# BusPirate-ng_v1_0.net
KiCad netlist of a schematic drawn in EAGLE
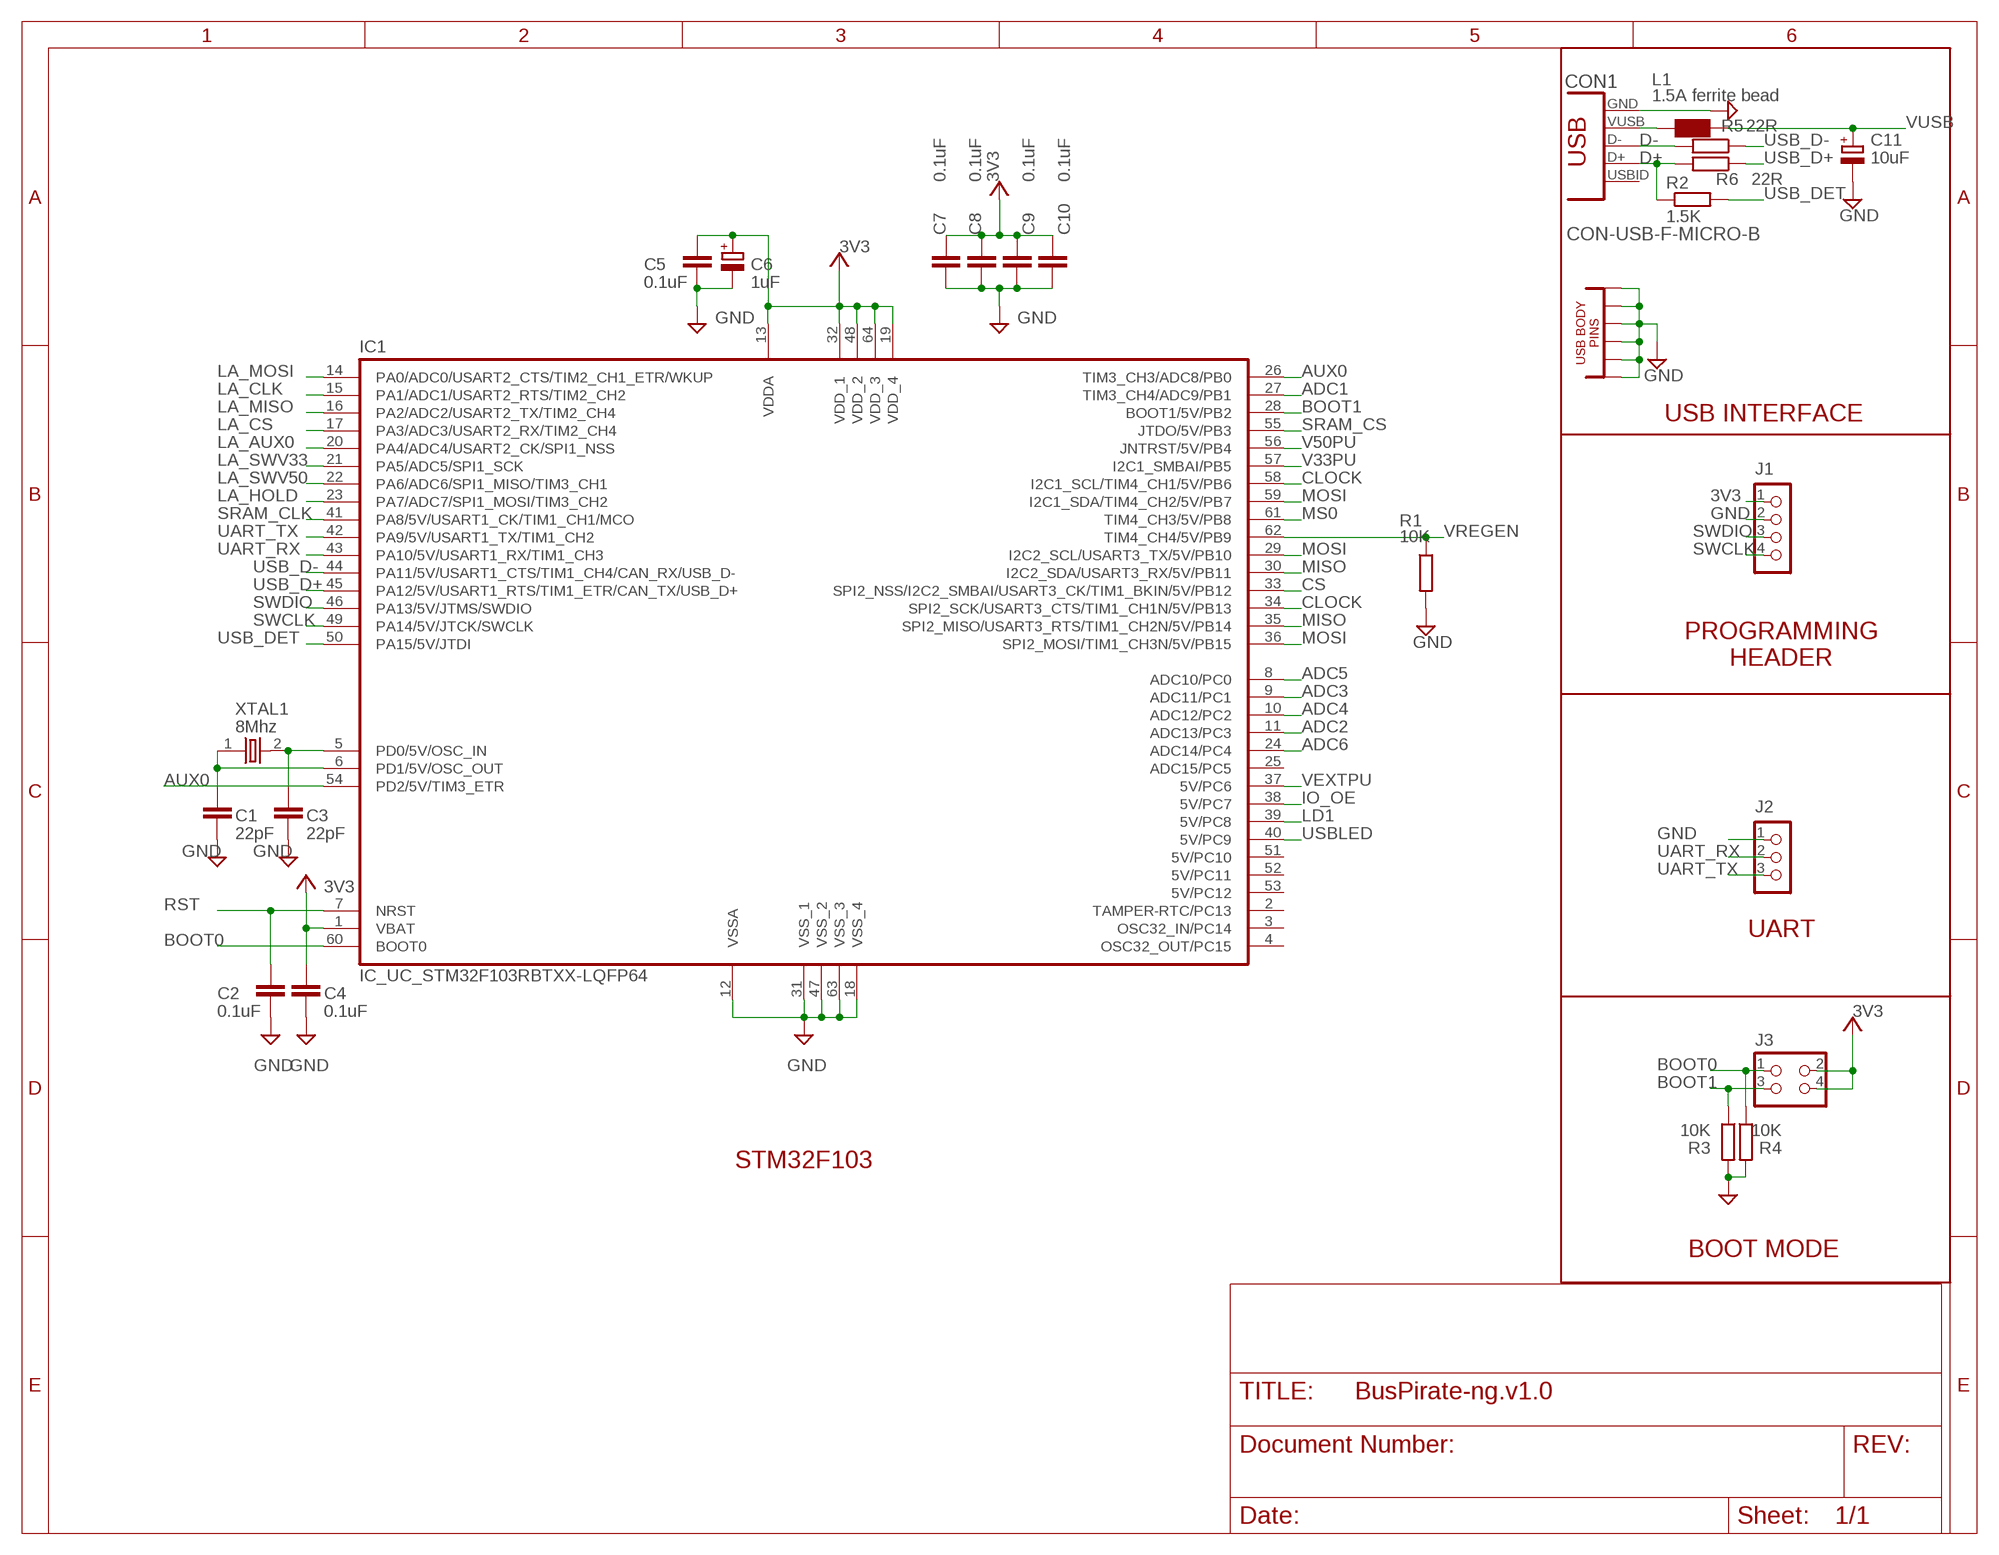
[diagram p0: schematic, sheet 1, part 1 of 2]
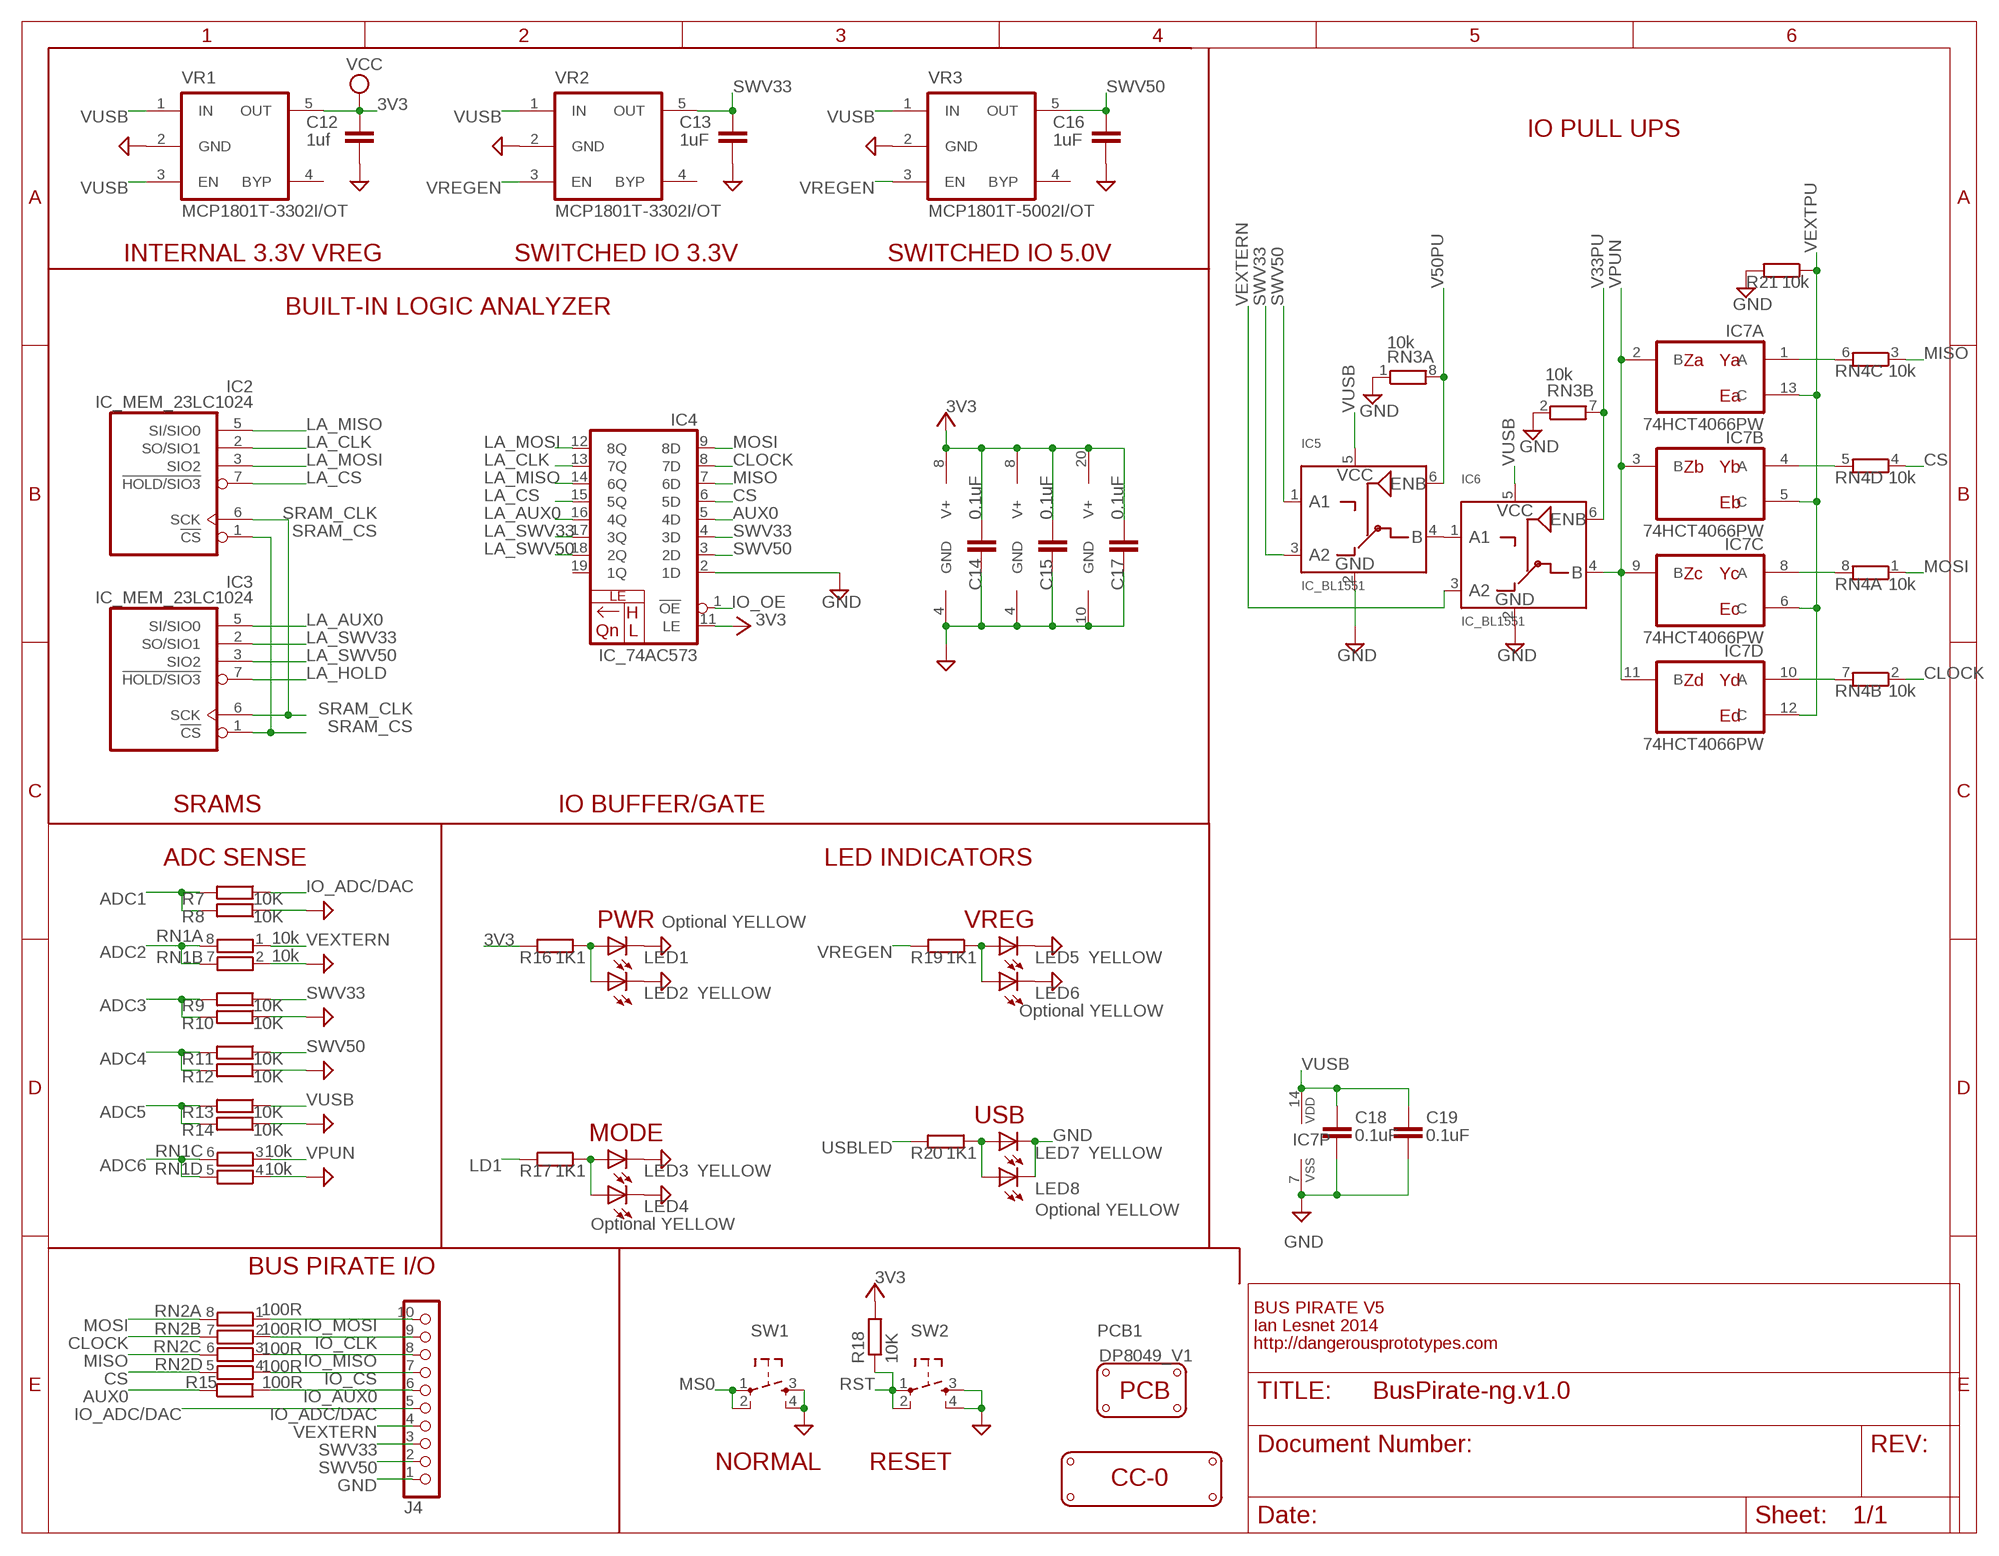
[diagram p1: schematic, sheet 1, part 2 of 2]

(export (version "E")
  (design (tool "Eeschema 10.0.6"))
  (components
    (comp (ref "C1")
      (value "22pF")
      (footprint "eagle-import:C0603")
      (libsource (lib "eagle-import") (part "C-EUC0603"))
    )
    (comp (ref "C2")
      (value "0.1uF")
      (footprint "eagle-import:C0603")
      (libsource (lib "eagle-import") (part "C-EUC0603"))
    )
    (comp (ref "C3")
      (value "22pF")
      (footprint "eagle-import:C0603")
      (libsource (lib "eagle-import") (part "C-EUC0603"))
    )
    (comp (ref "C4")
      (value "0.1uF")
      (footprint "eagle-import:C0603")
      (libsource (lib "eagle-import") (part "C-EUC0603"))
    )
    (comp (ref "C5")
      (value "0.1uF")
      (footprint "eagle-import:C0603")
      (libsource (lib "eagle-import") (part "C-EUC0603"))
    )
    (comp (ref "C6")
      (value "1uF")
      (footprint "eagle-import:SMC_A")
      (libsource (lib "eagle-import") (part "CPOL-EUSMCA"))
    )
    (comp (ref "C7")
      (value "0.1uF")
      (footprint "eagle-import:C0603")
      (libsource (lib "eagle-import") (part "C-EUC0603"))
    )
    (comp (ref "C8")
      (value "0.1uF")
      (footprint "eagle-import:C0603")
      (libsource (lib "eagle-import") (part "C-EUC0603"))
    )
    (comp (ref "C9")
      (value "0.1uF")
      (footprint "eagle-import:C0603")
      (libsource (lib "eagle-import") (part "C-EUC0603"))
    )
    (comp (ref "C10")
      (value "0.1uF")
      (footprint "eagle-import:C0603")
      (libsource (lib "eagle-import") (part "C-EUC0603"))
    )
    (comp (ref "C11")
      (value "10uF")
      (footprint "eagle-import:SMC_A")
      (libsource (lib "eagle-import") (part "CPOL-EUSMCA"))
    )
    (comp (ref "C12")
      (value "1uf")
      (footprint "eagle-import:C0603")
      (libsource (lib "eagle-import") (part "C-EUC0603"))
    )
    (comp (ref "C13")
      (value "1uF")
      (footprint "eagle-import:C0603")
      (libsource (lib "eagle-import") (part "C-EUC0603"))
    )
    (comp (ref "C14")
      (value "0.1uF")
      (footprint "eagle-import:C0603")
      (libsource (lib "eagle-import") (part "C-EUC0603"))
    )
    (comp (ref "C15")
      (value "0.1uF")
      (footprint "eagle-import:C0603")
      (libsource (lib "eagle-import") (part "C-EUC0603"))
    )
    (comp (ref "C16")
      (value "1uF")
      (footprint "eagle-import:C0603")
      (libsource (lib "eagle-import") (part "C-EUC0603"))
    )
    (comp (ref "C17")
      (value "0.1uF")
      (footprint "eagle-import:C0603")
      (libsource (lib "eagle-import") (part "C-EUC0603"))
    )
    (comp (ref "C18")
      (value "0.1uF")
      (footprint "eagle-import:C0603")
      (libsource (lib "eagle-import") (part "C-EUC0603"))
    )
    (comp (ref "C19")
      (value "0.1uF")
      (footprint "eagle-import:C0603")
      (libsource (lib "eagle-import") (part "C-EUC0603"))
    )
    (comp (ref "CON1")
      (value "CON-USB-F-MICRO-B")
      (footprint "eagle-import:CON_USB_MICRO-B-1-MD05SMXXX-01")
      (libsource (lib "eagle-import") (part "CON-USB-F-MICRO-B"))
    )
    (comp (ref "IC1")
      (value "IC_UC_STM32F103RBTXX-LQFP64")
      (footprint "eagle-import:LQFP64")
      (libsource (lib "eagle-import") (part "IC_UC_STM32F103RBTXX-LQFP64"))
    )
    (comp (ref "IC2")
      (value "IC_MEM_23LC1024")
      (footprint "eagle-import:SOIC-8")
      (libsource (lib "eagle-import") (part "IC_MEM_23LC1024"))
    )
    (comp (ref "IC3")
      (value "IC_MEM_23LC1024")
      (footprint "eagle-import:SOIC-8")
      (libsource (lib "eagle-import") (part "IC_MEM_23LC1024"))
    )
    (comp (ref "IC4")
      (value "IC_74AC573")
      (footprint "eagle-import:TSSOP-20")
      (libsource (lib "eagle-import") (part "IC_74AC573-TSSOP-20"))
    )
    (comp (ref "IC5")
      (value "IC_BL1551")
      (footprint "eagle-import:SOT-363")
      (libsource (lib "eagle-import") (part "IC_BL1551"))
    )
    (comp (ref "IC6")
      (value "IC_BL1551")
      (footprint "eagle-import:SOT-363")
      (libsource (lib "eagle-import") (part "IC_BL1551"))
    )
    (comp (ref "IC7")
      (value "74HCT4066PW")
      (footprint "eagle-import:40XX_TSSOP14")
      (libsource (lib "eagle-import") (part "4066TS"))
    )
    (comp (ref "J1")
      (value "CON_HEADER_1X04")
      (footprint "eagle-import:M1X4")
      (libsource (lib "eagle-import") (part "CON_HEADER_1X04"))
    )
    (comp (ref "J2")
      (value "CON_HEADER_1X03-PTH")
      (footprint "eagle-import:M1X3")
      (libsource (lib "eagle-import") (part "CON_HEADER_1X03-PTH"))
    )
    (comp (ref "J3")
      (value "CON_HEADER_2X02-PTH")
      (footprint "eagle-import:M2X2")
      (libsource (lib "eagle-import") (part "CON_HEADER_2X02-PTH"))
    )
    (comp (ref "J4")
      (value "CON_HEADER_1X10-RIGHT_ANGLED_PTH_SHROUDED")
      (footprint "eagle-import:M1X10_MALE_RIGHT_ANGLES_PTH_SHROUDED")
      (libsource (lib "eagle-import") (part "CON_HEADER_1X10-RIGHT_ANGLED_PTH_SHROUDED"))
    )
    (comp (ref "L1")
      (value "1.5A ferrite bead")
      (footprint "eagle-import:WE-KI_0805_B")
      (libsource (lib "eagle-import") (part "WE-KIL_0805"))
    )
    (comp (ref "LED1")
      (value "Optional YELLOW")
      (footprint "eagle-import:LED-805")
      (libsource (lib "eagle-import") (part "LED-0805"))
    )
    (comp (ref "LED2")
      (value "YELLOW")
      (footprint "eagle-import:LED-805")
      (libsource (lib "eagle-import") (part "LED-0805"))
    )
    (comp (ref "LED3")
      (value "YELLOW")
      (footprint "eagle-import:LED-805")
      (libsource (lib "eagle-import") (part "LED-0805"))
    )
    (comp (ref "LED4")
      (value "Optional YELLOW")
      (footprint "eagle-import:LED-805")
      (libsource (lib "eagle-import") (part "LED-0805"))
    )
    (comp (ref "LED5")
      (value "YELLOW")
      (footprint "eagle-import:LED-805")
      (libsource (lib "eagle-import") (part "LED-0805"))
    )
    (comp (ref "LED6")
      (value "Optional YELLOW")
      (footprint "eagle-import:LED-805")
      (libsource (lib "eagle-import") (part "LED-0805"))
    )
    (comp (ref "LED7")
      (value "YELLOW")
      (footprint "eagle-import:LED-805")
      (libsource (lib "eagle-import") (part "LED-0805"))
    )
    (comp (ref "LED8")
      (value "Optional YELLOW")
      (footprint "eagle-import:LED-805")
      (libsource (lib "eagle-import") (part "LED-0805"))
    )
    (comp (ref "LOGO1")
      (value "LOGO_CC-0")
      (footprint "eagle-import:LOGO_CC-0")
      (libsource (lib "eagle-import") (part "LOGO_CC-0"))
    )
    (comp (ref "PCB1")
      (value "PCB_DP_RECTANGLE-80X49")
      (footprint "eagle-import:DP8049_V1")
      (fields (field (name "PCB_SIZE") "DP8049_V1"))
      (libsource (lib "eagle-import") (part "PCB_DP_RECTANGLE-80X49"))
    )
    (comp (ref "R1")
      (value "10K")
      (footprint "eagle-import:R603")
      (libsource (lib "eagle-import") (part "RESISTOR-0603"))
    )
    (comp (ref "R2")
      (value "1.5K")
      (footprint "eagle-import:R603")
      (libsource (lib "eagle-import") (part "dp_devices.v6_RESISTOR-0603"))
    )
    (comp (ref "R3")
      (value "10K")
      (footprint "eagle-import:R0603")
      (libsource (lib "eagle-import") (part "R-EU_R0603"))
    )
    (comp (ref "R4")
      (value "10K")
      (footprint "eagle-import:R0603")
      (libsource (lib "eagle-import") (part "R-EU_R0603"))
    )
    (comp (ref "R5")
      (value "22R")
      (footprint "eagle-import:R603")
      (libsource (lib "eagle-import") (part "dp_devices.v6_RESISTOR-0603"))
    )
    (comp (ref "R6")
      (value "22R")
      (footprint "eagle-import:R603")
      (libsource (lib "eagle-import") (part "dp_devices.v6_RESISTOR-0603"))
    )
    (comp (ref "R7")
      (value "10K")
      (footprint "eagle-import:R0603")
      (libsource (lib "eagle-import") (part "resistor_R-EU_R0603"))
    )
    (comp (ref "R8")
      (value "10K")
      (footprint "eagle-import:R0603")
      (libsource (lib "eagle-import") (part "resistor_R-EU_R0603"))
    )
    (comp (ref "R9")
      (value "10K")
      (footprint "eagle-import:R0603")
      (libsource (lib "eagle-import") (part "resistor_R-EU_R0603"))
    )
    (comp (ref "R10")
      (value "10K")
      (footprint "eagle-import:R0603")
      (libsource (lib "eagle-import") (part "resistor_R-EU_R0603"))
    )
    (comp (ref "R11")
      (value "10K")
      (footprint "eagle-import:R0603")
      (libsource (lib "eagle-import") (part "resistor_R-EU_R0603"))
    )
    (comp (ref "R12")
      (value "10K")
      (footprint "eagle-import:R0603")
      (libsource (lib "eagle-import") (part "resistor_R-EU_R0603"))
    )
    (comp (ref "R13")
      (value "10K")
      (footprint "eagle-import:R0603")
      (libsource (lib "eagle-import") (part "resistor_R-EU_R0603"))
    )
    (comp (ref "R14")
      (value "10K")
      (footprint "eagle-import:R0603")
      (libsource (lib "eagle-import") (part "resistor_R-EU_R0603"))
    )
    (comp (ref "R15")
      (value "100R")
      (footprint "eagle-import:R603")
      (libsource (lib "eagle-import") (part "dp_devices.v6_RESISTOR-0603"))
    )
    (comp (ref "R16")
      (value "1K1")
      (footprint "eagle-import:R603")
      (libsource (lib "eagle-import") (part "RESISTOR-0603"))
    )
    (comp (ref "R17")
      (value "1K1")
      (footprint "eagle-import:R603")
      (libsource (lib "eagle-import") (part "RESISTOR-0603"))
    )
    (comp (ref "R18")
      (value "10K")
      (footprint "eagle-import:R603")
      (libsource (lib "eagle-import") (part "dp_devices.v6_RESISTOR-0603"))
    )
    (comp (ref "R19")
      (value "1K1")
      (footprint "eagle-import:R603")
      (libsource (lib "eagle-import") (part "RESISTOR-0603"))
    )
    (comp (ref "R20")
      (value "1K1")
      (footprint "eagle-import:R603")
      (libsource (lib "eagle-import") (part "RESISTOR-0603"))
    )
    (comp (ref "R21")
      (value "10k")
      (footprint "eagle-import:R603")
      (libsource (lib "eagle-import") (part "RESISTOR-0603"))
    )
    (comp (ref "RN1")
      (value "10k")
      (footprint "eagle-import:RN8P-4R-CRA06S")
      (libsource (lib "eagle-import") (part "RNETWORK"))
    )
    (comp (ref "RN2")
      (value "100R")
      (footprint "eagle-import:RN8P-4R-CRA06S")
      (libsource (lib "eagle-import") (part "RNETWORK"))
    )
    (comp (ref "RN3")
      (value "10k")
      (footprint "eagle-import:RN8P-4R-CRA06S")
      (libsource (lib "eagle-import") (part "RNETWORK"))
    )
    (comp (ref "RN4")
      (value "10k")
      (footprint "eagle-import:RN8P-4R-CRA06S")
      (libsource (lib "eagle-import") (part "RNETWORK"))
    )
    (comp (ref "SW1")
      (value "SW_TACT_4P")
      (footprint "eagle-import:SW_TACT_SMALL")
      (libsource (lib "eagle-import") (part "SW_TACT_4P"))
    )
    (comp (ref "SW2")
      (value "SW_TACT_4P")
      (footprint "eagle-import:SW_TACT_SMALL")
      (libsource (lib "eagle-import") (part "SW_TACT_4P"))
    )
    (comp (ref "VR1")
      (value "MCP1801T-3302I/OT")
      (footprint "eagle-import:SOT-23-5@1")
      (libsource (lib "eagle-import") (part "MIC5205"))
    )
    (comp (ref "VR2")
      (value "MCP1801T-3302I/OT")
      (footprint "eagle-import:SOT-23-5@1")
      (libsource (lib "eagle-import") (part "MIC5205"))
    )
    (comp (ref "VR3")
      (value "MCP1801T-5002I/OT")
      (footprint "eagle-import:SOT-23-5@1")
      (libsource (lib "eagle-import") (part "MIC5205"))
    )
    (comp (ref "XTAL1")
      (value "8Mhz")
      (footprint "eagle-import:XTAL_4X6")
      (libsource (lib "eagle-import") (part "OSC-XTAL-12M"))
    )
  )
  (nets
    (net (code "1") (name "/ADC1") (class "Default")
      (node (ref "IC1") (pin "27") (pinfunction "TIM3_CH4/ADC9/PB1_27") (pintype "bidirectional"))
      (node (ref "R7") (pin "2") (pinfunction "2_2") (pintype "passive"))
      (node (ref "R8") (pin "2") (pinfunction "2_2") (pintype "passive"))
    )
    (net (code "2") (name "/ADC2") (class "Default")
      (node (ref "IC1") (pin "11") (pinfunction "ADC13/PC3_11") (pintype "bidirectional"))
      (node (ref "RN1") (pin "7") (pinfunction "2_7") (pintype "passive"))
      (node (ref "RN1") (pin "8") (pinfunction "2_8") (pintype "passive"))
    )
    (net (code "3") (name "/ADC3") (class "Default")
      (node (ref "IC1") (pin "9") (pinfunction "ADC11/PC1_9") (pintype "bidirectional"))
      (node (ref "R10") (pin "2") (pinfunction "2_2") (pintype "passive"))
      (node (ref "R9") (pin "2") (pinfunction "2_2") (pintype "passive"))
    )
    (net (code "4") (name "/ADC4") (class "Default")
      (node (ref "IC1") (pin "10") (pinfunction "ADC12/PC2_10") (pintype "bidirectional"))
      (node (ref "R11") (pin "2") (pinfunction "2_2") (pintype "passive"))
      (node (ref "R12") (pin "2") (pinfunction "2_2") (pintype "passive"))
    )
    (net (code "5") (name "/ADC5") (class "Default")
      (node (ref "IC1") (pin "8") (pinfunction "ADC10/PC0_8") (pintype "bidirectional"))
      (node (ref "R13") (pin "2") (pinfunction "2_2") (pintype "passive"))
      (node (ref "R14") (pin "2") (pinfunction "2_2") (pintype "passive"))
    )
    (net (code "6") (name "/ADC6") (class "Default")
      (node (ref "IC1") (pin "24") (pinfunction "ADC14/PC4_24") (pintype "bidirectional"))
      (node (ref "RN1") (pin "5") (pinfunction "2_5") (pintype "passive"))
      (node (ref "RN1") (pin "6") (pinfunction "2_6") (pintype "passive"))
    )
    (net (code "7") (name "/AUX0") (class "Default")
      (node (ref "IC1") (pin "26") (pinfunction "TIM3_CH3/ADC8/PB0_26") (pintype "bidirectional"))
      (node (ref "IC1") (pin "54") (pinfunction "PD2/5V/TIM3_ETR_54") (pintype "bidirectional"))
      (node (ref "IC4") (pin "5") (pinfunction "4D_5") (pintype "bidirectional"))
      (node (ref "R15") (pin "1") (pinfunction "1_1") (pintype "passive"))
    )
    (net (code "8") (name "/BOOT0") (class "Default")
      (node (ref "IC1") (pin "60") (pinfunction "BOOT0_60") (pintype "input"))
      (node (ref "J3") (pin "1") (pinfunction "1_1") (pintype "passive"))
      (node (ref "R4") (pin "1") (pinfunction "1_1") (pintype "passive"))
    )
    (net (code "9") (name "/BOOT1") (class "Default")
      (node (ref "IC1") (pin "28") (pinfunction "BOOT1/5V/PB2_28") (pintype "bidirectional"))
      (node (ref "J3") (pin "3") (pinfunction "3_3") (pintype "passive"))
      (node (ref "R3") (pin "1") (pinfunction "1_1") (pintype "passive"))
    )
    (net (code "10") (name "/CLOCK") (class "Default")
      (node (ref "IC1") (pin "34") (pinfunction "SPI2_SCK/USART3_CTS/TIM1_CH1N/5V/PB13_34") (pintype "bidirectional"))
      (node (ref "IC1") (pin "58") (pinfunction "I2C1_SCL/TIM4_CH1/5V/PB6_58") (pintype "bidirectional"))
      (node (ref "IC4") (pin "8") (pinfunction "7D_8") (pintype "bidirectional"))
      (node (ref "RN2") (pin "7") (pinfunction "2_7") (pintype "passive"))
      (node (ref "RN4") (pin "2") (pinfunction "1_2") (pintype "passive"))
    )
    (net (code "11") (name "/CS") (class "Default")
      (node (ref "IC1") (pin "33") (pinfunction "SPI2_NSS/I2C2_SMBAI/USART3_CK/TIM1_BKIN/5V/PB12_33") (pintype "bidirectional"))
      (node (ref "IC4") (pin "6") (pinfunction "5D_6") (pintype "bidirectional"))
      (node (ref "RN2") (pin "5") (pinfunction "2_5") (pintype "passive"))
      (node (ref "RN4") (pin "4") (pinfunction "1_4") (pintype "passive"))
    )
    (net (code "12") (name "/D+") (class "Default")
      (node (ref "CON1") (pin "P3") (pinfunction "D+_P3") (pintype "bidirectional"))
      (node (ref "R2") (pin "1") (pinfunction "1_1") (pintype "passive"))
      (node (ref "R6") (pin "2") (pinfunction "2_2") (pintype "passive"))
    )
    (net (code "13") (name "/D-") (class "Default")
      (node (ref "CON1") (pin "P2") (pinfunction "D-_P2") (pintype "bidirectional"))
      (node (ref "R5") (pin "2") (pinfunction "2_2") (pintype "passive"))
    )
    (net (code "14") (name "/IO_ADC{slash}DAC") (class "Default")
      (node (ref "J4") (pin "5") (pinfunction "5_5") (pintype "passive"))
      (node (ref "R7") (pin "1") (pinfunction "1_1") (pintype "passive"))
    )
    (net (code "15") (name "/IO_AUX0") (class "Default")
      (node (ref "J4") (pin "6") (pinfunction "6_6") (pintype "passive"))
      (node (ref "R15") (pin "2") (pinfunction "2_2") (pintype "passive"))
    )
    (net (code "16") (name "/IO_CLK") (class "Default")
      (node (ref "J4") (pin "9") (pinfunction "9_9") (pintype "passive"))
      (node (ref "RN2") (pin "2") (pinfunction "1_2") (pintype "passive"))
    )
    (net (code "17") (name "/IO_CS") (class "Default")
      (node (ref "J4") (pin "7") (pinfunction "7_7") (pintype "passive"))
      (node (ref "RN2") (pin "4") (pinfunction "1_4") (pintype "passive"))
    )
    (net (code "18") (name "/IO_MISO") (class "Default")
      (node (ref "J4") (pin "8") (pinfunction "8_8") (pintype "passive"))
      (node (ref "RN2") (pin "3") (pinfunction "1_3") (pintype "passive"))
    )
    (net (code "19") (name "/IO_MOSI") (class "Default")
      (node (ref "J4") (pin "10") (pinfunction "10_10") (pintype "passive"))
      (node (ref "RN2") (pin "1") (pinfunction "1_1") (pintype "passive"))
    )
    (net (code "20") (name "/IO_OE") (class "Default")
      (node (ref "IC1") (pin "38") (pinfunction "5V/PC7_38") (pintype "bidirectional"))
      (node (ref "IC4") (pin "1") (pinfunction "~{OE}_1") (pintype "input"))
    )
    (net (code "21") (name "/LA_AUX0") (class "Default")
      (node (ref "IC1") (pin "20") (pinfunction "PA4/ADC4/USART2_CK/SPI1_NSS_20") (pintype "bidirectional"))
      (node (ref "IC3") (pin "5") (pinfunction "SI/SIO0_5") (pintype "bidirectional"))
      (node (ref "IC4") (pin "16") (pinfunction "4Q_16") (pintype "bidirectional"))
    )
    (net (code "22") (name "/LA_CLK") (class "Default")
      (node (ref "IC1") (pin "15") (pinfunction "PA1/ADC1/USART2_RTS/TIM2_CH2_15") (pintype "bidirectional"))
      (node (ref "IC2") (pin "2") (pinfunction "SO/SIO1_2") (pintype "bidirectional"))
      (node (ref "IC4") (pin "13") (pinfunction "7Q_13") (pintype "bidirectional"))
    )
    (net (code "23") (name "/LA_CS") (class "Default")
      (node (ref "IC1") (pin "17") (pinfunction "PA3/ADC3/USART2_RX/TIM2_CH4_17") (pintype "bidirectional"))
      (node (ref "IC2") (pin "7") (pinfunction "~{HOLD/SIO3}_7") (pintype "input"))
      (node (ref "IC4") (pin "15") (pinfunction "5Q_15") (pintype "bidirectional"))
    )
    (net (code "24") (name "/LA_HOLD") (class "Default")
      (node (ref "IC1") (pin "23") (pinfunction "PA7/ADC7/SPI1_MOSI/TIM3_CH2_23") (pintype "bidirectional"))
      (node (ref "IC3") (pin "7") (pinfunction "~{HOLD/SIO3}_7") (pintype "input"))
    )
    (net (code "25") (name "/LA_MISO") (class "Default")
      (node (ref "IC1") (pin "16") (pinfunction "PA2/ADC2/USART2_TX/TIM2_CH4_16") (pintype "bidirectional"))
      (node (ref "IC2") (pin "5") (pinfunction "SI/SIO0_5") (pintype "bidirectional"))
      (node (ref "IC4") (pin "14") (pinfunction "6Q_14") (pintype "bidirectional"))
    )
    (net (code "26") (name "/LA_MOSI") (class "Default")
      (node (ref "IC1") (pin "14") (pinfunction "PA0/ADC0/USART2_CTS/TIM2_CH1_ETR/WKUP_14") (pintype "bidirectional"))
      (node (ref "IC2") (pin "3") (pinfunction "SIO2_3") (pintype "bidirectional"))
      (node (ref "IC4") (pin "12") (pinfunction "8Q_12") (pintype "bidirectional"))
    )
    (net (code "27") (name "/LA_SWV33") (class "Default")
      (node (ref "IC1") (pin "21") (pinfunction "PA5/ADC5/SPI1_SCK_21") (pintype "bidirectional"))
      (node (ref "IC3") (pin "2") (pinfunction "SO/SIO1_2") (pintype "bidirectional"))
      (node (ref "IC4") (pin "17") (pinfunction "3Q_17") (pintype "bidirectional"))
    )
    (net (code "28") (name "/LA_SWV50") (class "Default")
      (node (ref "IC1") (pin "22") (pinfunction "PA6/ADC6/SPI1_MISO/TIM3_CH1_22") (pintype "bidirectional"))
      (node (ref "IC3") (pin "3") (pinfunction "SIO2_3") (pintype "bidirectional"))
      (node (ref "IC4") (pin "18") (pinfunction "2Q_18") (pintype "bidirectional"))
    )
    (net (code "29") (name "/LD1") (class "Default")
      (node (ref "IC1") (pin "39") (pinfunction "5V/PC8_39") (pintype "bidirectional"))
      (node (ref "R17") (pin "2") (pinfunction "2_2") (pintype "passive"))
    )
    (net (code "30") (name "/MISO") (class "Default")
      (node (ref "IC1") (pin "30") (pinfunction "I2C2_SDA/USART3_RX/5V/PB11_30") (pintype "bidirectional"))
      (node (ref "IC1") (pin "35") (pinfunction "SPI2_MISO/USART3_RTS/TIM1_CH2N/5V/PB14_35") (pintype "bidirectional"))
      (node (ref "IC4") (pin "7") (pinfunction "6D_7") (pintype "bidirectional"))
      (node (ref "RN2") (pin "6") (pinfunction "2_6") (pintype "passive"))
      (node (ref "RN4") (pin "3") (pinfunction "1_3") (pintype "passive"))
    )
    (net (code "31") (name "/MOSI") (class "Default")
      (node (ref "IC1") (pin "29") (pinfunction "I2C2_SCL/USART3_TX/5V/PB10_29") (pintype "bidirectional"))
      (node (ref "IC1") (pin "36") (pinfunction "SPI2_MOSI/TIM1_CH3N/5V/PB15_36") (pintype "bidirectional"))
      (node (ref "IC1") (pin "59") (pinfunction "I2C1_SDA/TIM4_CH2/5V/PB7_59") (pintype "bidirectional"))
      (node (ref "IC4") (pin "9") (pinfunction "8D_9") (pintype "bidirectional"))
      (node (ref "RN2") (pin "8") (pinfunction "2_8") (pintype "passive"))
      (node (ref "RN4") (pin "1") (pinfunction "1_1") (pintype "passive"))
    )
    (net (code "32") (name "/MS0") (class "Default")
      (node (ref "IC1") (pin "61") (pinfunction "TIM4_CH3/5V/PB8_61") (pintype "bidirectional"))
      (node (ref "SW1") (pin "1") (pinfunction "1_1") (pintype "passive"))
      (node (ref "SW1") (pin "2") (pinfunction "2_2") (pintype "passive"))
    )
    (net (code "33") (name "/RST") (class "Default")
      (node (ref "C2") (pin "2") (pinfunction "2_2") (pintype "passive"))
      (node (ref "IC1") (pin "7") (pinfunction "NRST_7") (pintype "bidirectional"))
      (node (ref "R18") (pin "1") (pinfunction "1_1") (pintype "passive"))
      (node (ref "SW2") (pin "1") (pinfunction "1_1") (pintype "passive"))
      (node (ref "SW2") (pin "2") (pinfunction "2_2") (pintype "passive"))
    )
    (net (code "34") (name "/SRAM_CLK") (class "Default")
      (node (ref "IC1") (pin "41") (pinfunction "PA8/5V/USART1_CK/TIM1_CH1/MCO_41") (pintype "bidirectional"))
      (node (ref "IC2") (pin "6") (pinfunction "SCK_6") (pintype "input"))
      (node (ref "IC3") (pin "6") (pinfunction "SCK_6") (pintype "input"))
    )
    (net (code "35") (name "/SRAM_CS") (class "Default")
      (node (ref "IC1") (pin "55") (pinfunction "JTDO/5V/PB3_55") (pintype "bidirectional"))
      (node (ref "IC2") (pin "1") (pinfunction "~{CS}_1") (pintype "input"))
      (node (ref "IC3") (pin "1") (pinfunction "~{CS}_1") (pintype "input"))
    )
    (net (code "36") (name "/SWCLK") (class "Default")
      (node (ref "IC1") (pin "49") (pinfunction "PA14/5V/JTCK/SWCLK_49") (pintype "bidirectional"))
      (node (ref "J1") (pin "4") (pinfunction "4_4") (pintype "bidirectional"))
    )
    (net (code "37") (name "/SWDIO") (class "Default")
      (node (ref "IC1") (pin "46") (pinfunction "PA13/5V/JTMS/SWDIO_46") (pintype "bidirectional"))
      (node (ref "J1") (pin "3") (pinfunction "3_3") (pintype "bidirectional"))
    )
    (net (code "38") (name "/SWV33") (class "Default")
      (node (ref "C13") (pin "1") (pinfunction "1_1") (pintype "passive"))
      (node (ref "IC4") (pin "4") (pinfunction "3D_4") (pintype "bidirectional"))
      (node (ref "IC5") (pin "3") (pinfunction "A2_3") (pintype "input"))
      (node (ref "J4") (pin "3") (pinfunction "3_3") (pintype "passive"))
      (node (ref "R9") (pin "1") (pinfunction "1_1") (pintype "passive"))
      (node (ref "VR2") (pin "5") (pinfunction "OUT_5") (pintype "bidirectional"))
    )
    (net (code "39") (name "/SWV50") (class "Default")
      (node (ref "C16") (pin "1") (pinfunction "1_1") (pintype "passive"))
      (node (ref "IC4") (pin "3") (pinfunction "2D_3") (pintype "bidirectional"))
      (node (ref "IC5") (pin "1") (pinfunction "A1_1") (pintype "input"))
      (node (ref "J4") (pin "2") (pinfunction "2_2") (pintype "passive"))
      (node (ref "R11") (pin "1") (pinfunction "1_1") (pintype "passive"))
      (node (ref "VR3") (pin "5") (pinfunction "OUT_5") (pintype "bidirectional"))
    )
    (net (code "40") (name "/UART_RX") (class "Default")
      (node (ref "IC1") (pin "43") (pinfunction "PA10/5V/USART1_RX/TIM1_CH3_43") (pintype "bidirectional"))
      (node (ref "J2") (pin "2") (pinfunction "2_2") (pintype "bidirectional"))
    )
    (net (code "41") (name "/UART_TX") (class "Default")
      (node (ref "IC1") (pin "42") (pinfunction "PA9/5V/USART1_TX/TIM1_CH2_42") (pintype "bidirectional"))
      (node (ref "J2") (pin "3") (pinfunction "3_3") (pintype "bidirectional"))
    )
    (net (code "42") (name "/USBLED") (class "Default")
      (node (ref "IC1") (pin "40") (pinfunction "5V/PC9_40") (pintype "bidirectional"))
      (node (ref "R20") (pin "2") (pinfunction "2_2") (pintype "passive"))
    )
    (net (code "43") (name "/USB_D+") (class "Default")
      (node (ref "IC1") (pin "45") (pinfunction "PA12/5V/USART1_RTS/TIM1_ETR/CAN_TX/USB_D+_45") (pintype "bidirectional"))
      (node (ref "R6") (pin "1") (pinfunction "1_1") (pintype "passive"))
    )
    (net (code "44") (name "/USB_D-") (class "Default")
      (node (ref "IC1") (pin "44") (pinfunction "PA11/5V/USART1_CTS/TIM1_CH4/CAN_RX/USB_D-_44") (pintype "bidirectional"))
      (node (ref "R5") (pin "1") (pinfunction "1_1") (pintype "passive"))
    )
    (net (code "45") (name "/USB_DET") (class "Default")
      (node (ref "IC1") (pin "50") (pinfunction "PA15/5V/JTDI_50") (pintype "bidirectional"))
      (node (ref "R2") (pin "2") (pinfunction "2_2") (pintype "passive"))
    )
    (net (code "46") (name "/V33PU") (class "Default")
      (node (ref "IC1") (pin "57") (pinfunction "I2C1_SMBAI/PB5_57") (pintype "bidirectional"))
      (node (ref "IC6") (pin "6") (pinfunction "ENB_6") (pintype "input"))
      (node (ref "RN3") (pin "7") (pinfunction "2_7") (pintype "passive"))
    )
    (net (code "47") (name "/V50PU") (class "Default")
      (node (ref "IC1") (pin "56") (pinfunction "JNTRST/5V/PB4_56") (pintype "bidirectional"))
      (node (ref "IC5") (pin "6") (pinfunction "ENB_6") (pintype "input"))
      (node (ref "RN3") (pin "8") (pinfunction "2_8") (pintype "passive"))
    )
    (net (code "48") (name "/VEXTERN") (class "Default")
      (node (ref "IC6") (pin "3") (pinfunction "A2_3") (pintype "input"))
      (node (ref "J4") (pin "4") (pinfunction "4_4") (pintype "passive"))
      (node (ref "RN1") (pin "1") (pinfunction "1_1") (pintype "passive"))
    )
    (net (code "49") (name "/VEXTPU") (class "Default")
      (node (ref "IC1") (pin "37") (pinfunction "5V/PC6_37") (pintype "bidirectional"))
      (node (ref "IC7") (pin "12") (pinfunction "C_12") (pintype "input"))
      (node (ref "IC7") (pin "13") (pinfunction "C_13") (pintype "input"))
      (node (ref "IC7") (pin "5") (pinfunction "C_5") (pintype "input"))
      (node (ref "IC7") (pin "6") (pinfunction "C_6") (pintype "input"))
      (node (ref "R21") (pin "1") (pinfunction "1_1") (pintype "passive"))
    )
    (net (code "50") (name "/VPUN") (class "Default")
      (node (ref "IC6") (pin "4") (pinfunction "B_4") (pintype "output"))
      (node (ref "IC7") (pin "11") (pinfunction "B_11") (pintype "tri_state"))
      (node (ref "IC7") (pin "2") (pinfunction "B_2") (pintype "tri_state"))
      (node (ref "IC7") (pin "3") (pinfunction "B_3") (pintype "tri_state"))
      (node (ref "IC7") (pin "9") (pinfunction "B_9") (pintype "tri_state"))
      (node (ref "RN1") (pin "3") (pinfunction "1_3") (pintype "passive"))
    )
    (net (code "51") (name "/VREGEN") (class "Default")
      (node (ref "IC1") (pin "62") (pinfunction "TIM4_CH4/5V/PB9_62") (pintype "bidirectional"))
      (node (ref "R1") (pin "1") (pinfunction "1_1") (pintype "passive"))
      (node (ref "R19") (pin "2") (pinfunction "2_2") (pintype "passive"))
      (node (ref "VR2") (pin "3") (pinfunction "EN_3") (pintype "bidirectional"))
      (node (ref "VR3") (pin "3") (pinfunction "EN_3") (pintype "bidirectional"))
    )
    (net (code "52") (name "/VUSB") (class "Default")
      (node (ref "C11") (pin "+") (pinfunction "+_+") (pintype "passive"))
      (node (ref "C18") (pin "1") (pinfunction "1_1") (pintype "passive"))
      (node (ref "C19") (pin "1") (pinfunction "1_1") (pintype "passive"))
      (node (ref "IC5") (pin "5") (pinfunction "VCC_5") (pintype "power_in"))
      (node (ref "IC6") (pin "5") (pinfunction "VCC_5") (pintype "power_in"))
      (node (ref "IC7") (pin "14") (pinfunction "VDD_14") (pintype "power_in"))
      (node (ref "L1") (pin "1") (pinfunction "2_1") (pintype "passive"))
      (node (ref "R13") (pin "1") (pinfunction "1_1") (pintype "passive"))
      (node (ref "VR1") (pin "1") (pinfunction "IN_1") (pintype "bidirectional"))
      (node (ref "VR1") (pin "3") (pinfunction "EN_3") (pintype "bidirectional"))
      (node (ref "VR2") (pin "1") (pinfunction "IN_1") (pintype "bidirectional"))
      (node (ref "VR3") (pin "1") (pinfunction "IN_1") (pintype "bidirectional"))
    )
    (net (code "53") (name "GND") (class "Default")
      (node (ref "C1") (pin "1") (pinfunction "1_1") (pintype "passive"))
      (node (ref "C10") (pin "1") (pinfunction "1_1") (pintype "passive"))
      (node (ref "C11") (pin "-") (pinfunction "-_-") (pintype "passive"))
      (node (ref "C12") (pin "2") (pinfunction "2_2") (pintype "passive"))
      (node (ref "C13") (pin "2") (pinfunction "2_2") (pintype "passive"))
      (node (ref "C14") (pin "2") (pinfunction "2_2") (pintype "passive"))
      (node (ref "C15") (pin "2") (pinfunction "2_2") (pintype "passive"))
      (node (ref "C16") (pin "2") (pinfunction "2_2") (pintype "passive"))
      (node (ref "C17") (pin "2") (pinfunction "2_2") (pintype "passive"))
      (node (ref "C18") (pin "2") (pinfunction "2_2") (pintype "passive"))
      (node (ref "C19") (pin "2") (pinfunction "2_2") (pintype "passive"))
      (node (ref "C2") (pin "1") (pinfunction "1_1") (pintype "passive"))
      (node (ref "C3") (pin "1") (pinfunction "1_1") (pintype "passive"))
      (node (ref "C4") (pin "1") (pinfunction "1_1") (pintype "passive"))
      (node (ref "C5") (pin "1") (pinfunction "1_1") (pintype "passive"))
      (node (ref "C6") (pin "-") (pinfunction "-_-") (pintype "passive"))
      (node (ref "C7") (pin "1") (pinfunction "1_1") (pintype "passive"))
      (node (ref "C8") (pin "1") (pinfunction "1_1") (pintype "passive"))
      (node (ref "C9") (pin "1") (pinfunction "1_1") (pintype "passive"))
      (node (ref "CON1") (pin "GND1") (pinfunction "P$1_GND1") (pintype "passive"))
      (node (ref "CON1") (pin "GND2") (pinfunction "P$2_GND2") (pintype "passive"))
      (node (ref "CON1") (pin "GND3") (pinfunction "P$3_GND3") (pintype "passive"))
      (node (ref "CON1") (pin "GND4") (pinfunction "P$4_GND4") (pintype "passive"))
      (node (ref "CON1") (pin "GND5") (pinfunction "P$5_GND5") (pintype "passive"))
      (node (ref "CON1") (pin "GND6") (pinfunction "P$6_GND6") (pintype "passive"))
      (node (ref "CON1") (pin "P5") (pinfunction "GND_P5") (pintype "bidirectional"))
      (node (ref "IC1") (pin "12") (pinfunction "VSSA_12") (pintype "power_in"))
      (node (ref "IC1") (pin "18") (pinfunction "VSS_4_18") (pintype "power_in"))
      (node (ref "IC1") (pin "31") (pinfunction "VSS_1_31") (pintype "power_in"))
      (node (ref "IC1") (pin "47") (pinfunction "VSS_2_47") (pintype "power_in"))
      (node (ref "IC1") (pin "63") (pinfunction "VSS_3_63") (pintype "power_in"))
      (node (ref "IC2") (pin "4") (pinfunction "GND_4") (pintype "power_in"))
      (node (ref "IC3") (pin "4") (pinfunction "GND_4") (pintype "power_in"))
      (node (ref "IC4") (pin "10") (pinfunction "GND_10") (pintype "power_in"))
      (node (ref "IC4") (pin "2") (pinfunction "1D_2") (pintype "bidirectional"))
      (node (ref "IC5") (pin "2") (pinfunction "GND_2") (pintype "power_in"))
      (node (ref "IC6") (pin "2") (pinfunction "GND_2") (pintype "power_in"))
      (node (ref "IC7") (pin "7") (pinfunction "VSS_7") (pintype "power_in"))
      (node (ref "J1") (pin "2") (pinfunction "2_2") (pintype "bidirectional"))
      (node (ref "J2") (pin "1") (pinfunction "1_1") (pintype "bidirectional"))
      (node (ref "J4") (pin "1") (pinfunction "1_1") (pintype "passive"))
      (node (ref "LED1") (pin "C") (pinfunction "C_C") (pintype "passive"))
      (node (ref "LED2") (pin "C") (pinfunction "C_C") (pintype "passive"))
      (node (ref "LED3") (pin "C") (pinfunction "C_C") (pintype "passive"))
      (node (ref "LED4") (pin "C") (pinfunction "C_C") (pintype "passive"))
      (node (ref "LED5") (pin "C") (pinfunction "C_C") (pintype "passive"))
      (node (ref "LED6") (pin "C") (pinfunction "C_C") (pintype "passive"))
      (node (ref "LED7") (pin "C") (pinfunction "C_C") (pintype "passive"))
      (node (ref "LED8") (pin "C") (pinfunction "C_C") (pintype "passive"))
      (node (ref "R1") (pin "2") (pinfunction "2_2") (pintype "passive"))
      (node (ref "R10") (pin "1") (pinfunction "1_1") (pintype "passive"))
      (node (ref "R12") (pin "1") (pinfunction "1_1") (pintype "passive"))
      (node (ref "R14") (pin "1") (pinfunction "1_1") (pintype "passive"))
      (node (ref "R21") (pin "2") (pinfunction "2_2") (pintype "passive"))
      (node (ref "R3") (pin "2") (pinfunction "2_2") (pintype "passive"))
      (node (ref "R4") (pin "2") (pinfunction "2_2") (pintype "passive"))
      (node (ref "R8") (pin "1") (pinfunction "1_1") (pintype "passive"))
      (node (ref "RN1") (pin "2") (pinfunction "1_2") (pintype "passive"))
      (node (ref "RN1") (pin "4") (pinfunction "1_4") (pintype "passive"))
      (node (ref "RN3") (pin "1") (pinfunction "1_1") (pintype "passive"))
      (node (ref "RN3") (pin "2") (pinfunction "1_2") (pintype "passive"))
      (node (ref "SW1") (pin "3") (pinfunction "3_3") (pintype "passive"))
      (node (ref "SW1") (pin "4") (pinfunction "4_4") (pintype "passive"))
      (node (ref "SW2") (pin "3") (pinfunction "3_3") (pintype "passive"))
      (node (ref "SW2") (pin "4") (pinfunction "4_4") (pintype "passive"))
      (node (ref "VR1") (pin "2") (pinfunction "GND_2") (pintype "bidirectional"))
      (node (ref "VR2") (pin "2") (pinfunction "GND_2") (pintype "bidirectional"))
      (node (ref "VR3") (pin "2") (pinfunction "GND_2") (pintype "bidirectional"))
    )
    (net (code "54") (name "Net-(CON1A-VUSB)") (class "Default")
      (node (ref "CON1") (pin "P1") (pinfunction "VUSB_P1") (pintype "bidirectional"))
      (node (ref "L1") (pin "2") (pinfunction "1_2") (pintype "passive"))
    )
    (net (code "55") (name "Net-(IC1-PD0{slash}5V{slash}OSC_IN)") (class "Default")
      (node (ref "C3") (pin "2") (pinfunction "2_2") (pintype "passive"))
      (node (ref "IC1") (pin "5") (pinfunction "PD0/5V/OSC_IN_5") (pintype "input"))
      (node (ref "XTAL1") (pin "2") (pinfunction "2_2") (pintype "passive"))
    )
    (net (code "56") (name "Net-(IC1-PD1{slash}5V{slash}OSC_OUT)") (class "Default")
      (node (ref "C1") (pin "2") (pinfunction "2_2") (pintype "passive"))
      (node (ref "IC1") (pin "6") (pinfunction "PD1/5V/OSC_OUT_6") (pintype "output"))
      (node (ref "XTAL1") (pin "1") (pinfunction "1_1") (pintype "passive"))
    )
    (net (code "57") (name "Net-(IC5-B)") (class "Default")
      (node (ref "IC5") (pin "4") (pinfunction "B_4") (pintype "output"))
      (node (ref "IC6") (pin "1") (pinfunction "A1_1") (pintype "input"))
    )
    (net (code "58") (name "Net-(IC7A-A)") (class "Default")
      (node (ref "IC7") (pin "1") (pinfunction "A_1") (pintype "tri_state"))
      (node (ref "RN4") (pin "6") (pinfunction "2_6") (pintype "passive"))
    )
    (net (code "59") (name "Net-(IC7B-A)") (class "Default")
      (node (ref "IC7") (pin "4") (pinfunction "A_4") (pintype "tri_state"))
      (node (ref "RN4") (pin "5") (pinfunction "2_5") (pintype "passive"))
    )
    (net (code "60") (name "Net-(IC7C-A)") (class "Default")
      (node (ref "IC7") (pin "8") (pinfunction "A_8") (pintype "tri_state"))
      (node (ref "RN4") (pin "8") (pinfunction "2_8") (pintype "passive"))
    )
    (net (code "61") (name "Net-(IC7D-A)") (class "Default")
      (node (ref "IC7") (pin "10") (pinfunction "A_10") (pintype "tri_state"))
      (node (ref "RN4") (pin "7") (pinfunction "2_7") (pintype "passive"))
    )
    (net (code "62") (name "Net-(LED1-PadA)") (class "Default")
      (node (ref "LED1") (pin "A") (pinfunction "A_A") (pintype "passive"))
      (node (ref "LED2") (pin "A") (pinfunction "A_A") (pintype "passive"))
      (node (ref "R16") (pin "1") (pinfunction "1_1") (pintype "passive"))
    )
    (net (code "63") (name "Net-(LED3-PadA)") (class "Default")
      (node (ref "LED3") (pin "A") (pinfunction "A_A") (pintype "passive"))
      (node (ref "LED4") (pin "A") (pinfunction "A_A") (pintype "passive"))
      (node (ref "R17") (pin "1") (pinfunction "1_1") (pintype "passive"))
    )
    (net (code "64") (name "Net-(LED5-PadA)") (class "Default")
      (node (ref "LED5") (pin "A") (pinfunction "A_A") (pintype "passive"))
      (node (ref "LED6") (pin "A") (pinfunction "A_A") (pintype "passive"))
      (node (ref "R19") (pin "1") (pinfunction "1_1") (pintype "passive"))
    )
    (net (code "65") (name "Net-(LED7-PadA)") (class "Default")
      (node (ref "LED7") (pin "A") (pinfunction "A_A") (pintype "passive"))
      (node (ref "LED8") (pin "A") (pinfunction "A_A") (pintype "passive"))
      (node (ref "R20") (pin "1") (pinfunction "1_1") (pintype "passive"))
    )
    (net (code "66") (name "V+") (class "Default")
      (node (ref "C10") (pin "2") (pinfunction "2_2") (pintype "passive"))
      (node (ref "C12") (pin "1") (pinfunction "1_1") (pintype "passive"))
      (node (ref "C14") (pin "1") (pinfunction "1_1") (pintype "passive"))
      (node (ref "C15") (pin "1") (pinfunction "1_1") (pintype "passive"))
      (node (ref "C17") (pin "1") (pinfunction "1_1") (pintype "passive"))
      (node (ref "C4") (pin "2") (pinfunction "2_2") (pintype "passive"))
      (node (ref "C5") (pin "2") (pinfunction "2_2") (pintype "passive"))
      (node (ref "C6") (pin "+") (pinfunction "+_+") (pintype "passive"))
      (node (ref "C7") (pin "2") (pinfunction "2_2") (pintype "passive"))
      (node (ref "C8") (pin "2") (pinfunction "2_2") (pintype "passive"))
      (node (ref "C9") (pin "2") (pinfunction "2_2") (pintype "passive"))
      (node (ref "IC1") (pin "1") (pinfunction "VBAT_1") (pintype "power_in"))
      (node (ref "IC1") (pin "13") (pinfunction "VDDA_13") (pintype "power_in"))
      (node (ref "IC1") (pin "19") (pinfunction "VDD_4_19") (pintype "power_in"))
      (node (ref "IC1") (pin "32") (pinfunction "VDD_1_32") (pintype "power_in"))
      (node (ref "IC1") (pin "48") (pinfunction "VDD_2_48") (pintype "power_in"))
      (node (ref "IC1") (pin "64") (pinfunction "VDD_3_64") (pintype "power_in"))
      (node (ref "IC2") (pin "8") (pinfunction "V+_8") (pintype "power_in"))
      (node (ref "IC3") (pin "8") (pinfunction "V+_8") (pintype "power_in"))
      (node (ref "IC4") (pin "11") (pinfunction "LE_11") (pintype "input"))
      (node (ref "IC4") (pin "20") (pinfunction "V+_20") (pintype "power_in"))
      (node (ref "J1") (pin "1") (pinfunction "1_1") (pintype "bidirectional"))
      (node (ref "J3") (pin "2") (pinfunction "2_2") (pintype "passive"))
      (node (ref "J3") (pin "4") (pinfunction "4_4") (pintype "passive"))
      (node (ref "R16") (pin "2") (pinfunction "2_2") (pintype "passive"))
      (node (ref "R18") (pin "2") (pinfunction "2_2") (pintype "passive"))
      (node (ref "VR1") (pin "5") (pinfunction "OUT_5") (pintype "bidirectional"))
    )
    (net (code "67") (name "unconnected-(CON1A-USBID-PadP4)") (class "Default")
      (node (ref "CON1") (pin "P4") (pinfunction "USBID_P4") (pintype "bidirectional"))
    )
    (net (code "68") (name "unconnected-(IC1-5V{slash}PC10-Pad51)") (class "Default")
      (node (ref "IC1") (pin "51") (pinfunction "5V/PC10_51") (pintype "bidirectional"))
    )
    (net (code "69") (name "unconnected-(IC1-5V{slash}PC11-Pad52)") (class "Default")
      (node (ref "IC1") (pin "52") (pinfunction "5V/PC11_52") (pintype "bidirectional"))
    )
    (net (code "70") (name "unconnected-(IC1-5V{slash}PC12-Pad53)") (class "Default")
      (node (ref "IC1") (pin "53") (pinfunction "5V/PC12_53") (pintype "bidirectional"))
    )
    (net (code "71") (name "unconnected-(IC1-ADC15{slash}PC5-Pad25)") (class "Default")
      (node (ref "IC1") (pin "25") (pinfunction "ADC15/PC5_25") (pintype "bidirectional"))
    )
    (net (code "72") (name "unconnected-(IC1-OSC32_IN{slash}PC14-Pad3)") (class "Default")
      (node (ref "IC1") (pin "3") (pinfunction "OSC32_IN/PC14_3") (pintype "bidirectional"))
    )
    (net (code "73") (name "unconnected-(IC1-OSC32_OUT{slash}PC15-Pad4)") (class "Default")
      (node (ref "IC1") (pin "4") (pinfunction "OSC32_OUT/PC15_4") (pintype "bidirectional"))
    )
    (net (code "74") (name "unconnected-(IC1-TAMPER-RTC{slash}PC13-Pad2)") (class "Default")
      (node (ref "IC1") (pin "2") (pinfunction "TAMPER-RTC/PC13_2") (pintype "bidirectional"))
    )
    (net (code "75") (name "unconnected-(IC4A-1Q-Pad19)") (class "Default")
      (node (ref "IC4") (pin "19") (pinfunction "1Q_19") (pintype "bidirectional"))
    )
    (net (code "76") (name "unconnected-(VR1-BYP-Pad4)") (class "Default")
      (node (ref "VR1") (pin "4") (pinfunction "BYP_4") (pintype "bidirectional"))
    )
    (net (code "77") (name "unconnected-(VR2-BYP-Pad4)") (class "Default")
      (node (ref "VR2") (pin "4") (pinfunction "BYP_4") (pintype "bidirectional"))
    )
    (net (code "78") (name "unconnected-(VR3-BYP-Pad4)") (class "Default")
      (node (ref "VR3") (pin "4") (pinfunction "BYP_4") (pintype "bidirectional"))
    )
  )
)
